# REV_LIMTER_ARDUINO_NANO.net
KiCad netlist of a schematic drawn in EAGLE
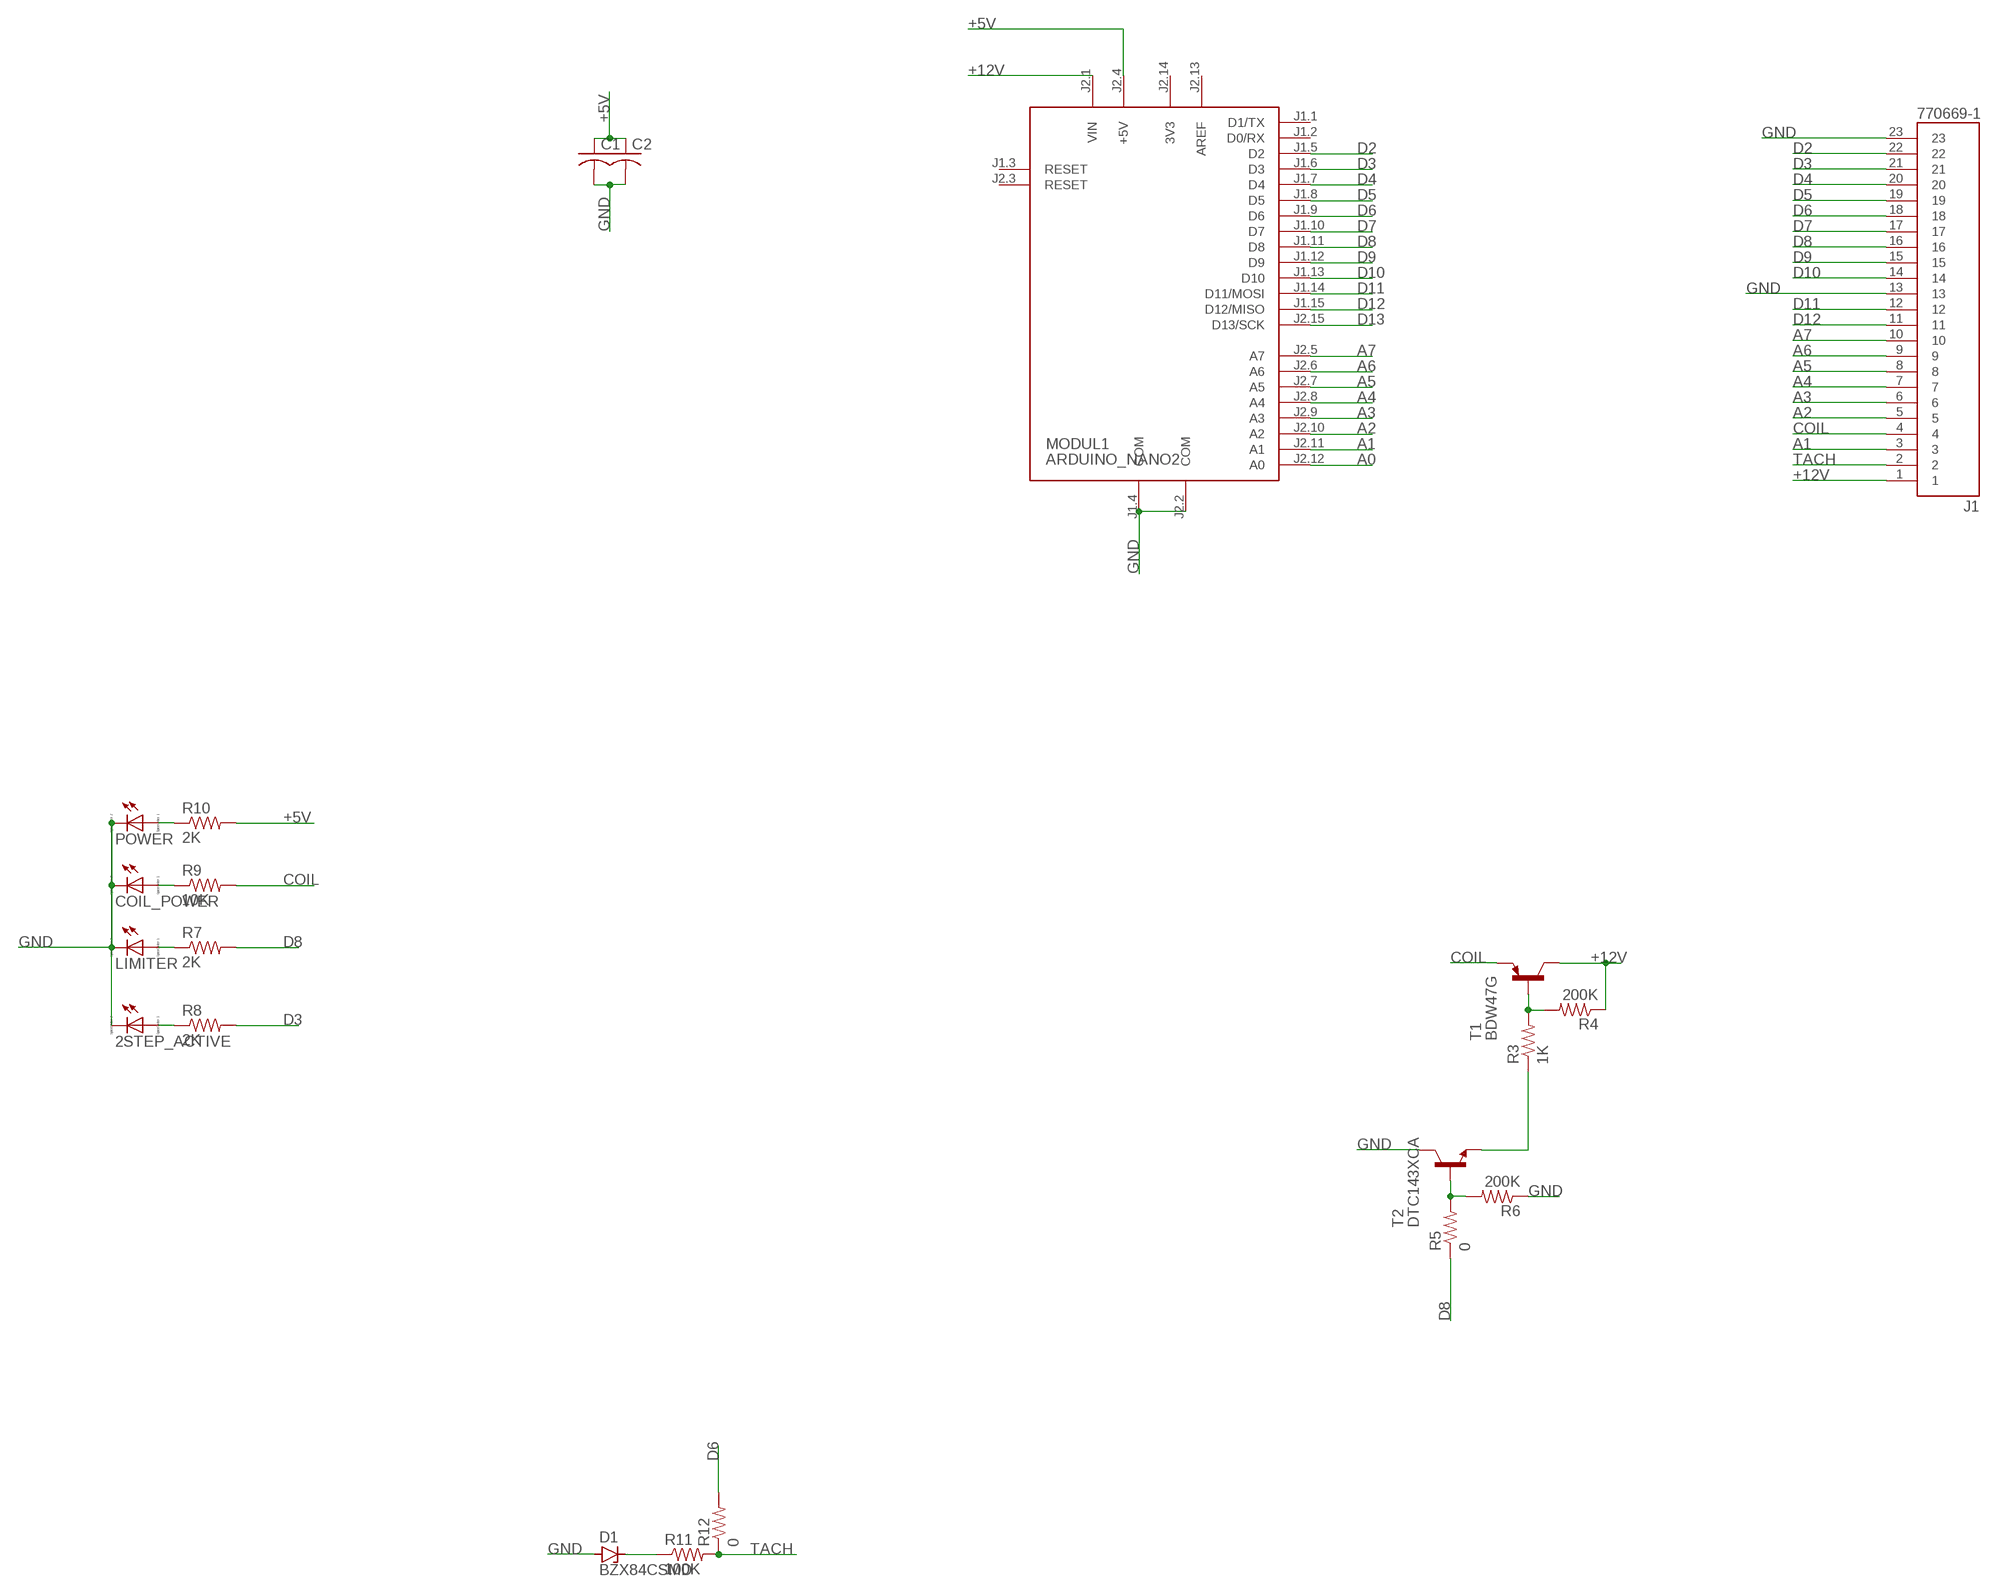
[diagram p0: schematic, sheet 1]

(export (version "E")
  (design (tool "Eeschema 10.0.6"))
  (components
    (comp (ref "2STEP_ACTIVE")
      (value "LED_E")
      (footprint "eagle-import:LED_1206")
      (libsource (lib "eagle-import") (part "LED_E"))
    )
    (comp (ref "C1")
      (value "C-USC1206")
      (footprint "eagle-import:C1206")
      (libsource (lib "eagle-import") (part "C-USC1206"))
    )
    (comp (ref "C2")
      (value "C-USC1206")
      (footprint "eagle-import:C1206")
      (libsource (lib "eagle-import") (part "C-USC1206"))
    )
    (comp (ref "COIL_POWER")
      (value "LED_E")
      (footprint "eagle-import:LED_1206")
      (libsource (lib "eagle-import") (part "LED_E"))
    )
    (comp (ref "D1")
      (value "BZX84CSMD")
      (footprint "eagle-import:TO236")
      (libsource (lib "eagle-import") (part "BZX84CSMD"))
    )
    (comp (ref "J1")
      (value "770669-1")
      (footprint "eagle-import:TE_770669-1")
      (fields (field (name "MF") "TE Connectivity"))
      (libsource (lib "eagle-import") (part "770669-1"))
    )
    (comp (ref "LIMITER")
      (value "LED_E")
      (footprint "eagle-import:LED_1206")
      (libsource (lib "eagle-import") (part "LED_E"))
    )
    (comp (ref "MODUL1")
      (value "ARDUINO_NANO2")
      (footprint "eagle-import:ARDUINO_NANO2")
      (libsource (lib "eagle-import") (part "ARDUINO_NANO2"))
    )
    (comp (ref "POWER")
      (value "LED_E")
      (footprint "eagle-import:LED_1206")
      (libsource (lib "eagle-import") (part "LED_E"))
    )
    (comp (ref "R3")
      (value "1K")
      (footprint "eagle-import:M0805")
      (libsource (lib "eagle-import") (part "R-US_M0805"))
    )
    (comp (ref "R4")
      (value "200K")
      (footprint "eagle-import:M0805")
      (libsource (lib "eagle-import") (part "R-US_M0805"))
    )
    (comp (ref "R5")
      (value "0")
      (footprint "eagle-import:M0805")
      (libsource (lib "eagle-import") (part "R-US_M0805"))
    )
    (comp (ref "R6")
      (value "200K")
      (footprint "eagle-import:M0805")
      (libsource (lib "eagle-import") (part "R-US_M0805"))
    )
    (comp (ref "R7")
      (value "2K")
      (footprint "eagle-import:R1206")
      (libsource (lib "eagle-import") (part "R-US_R1206"))
    )
    (comp (ref "R8")
      (value "2K")
      (footprint "eagle-import:R1206")
      (libsource (lib "eagle-import") (part "R-US_R1206"))
    )
    (comp (ref "R9")
      (value "10K")
      (footprint "eagle-import:R1206")
      (libsource (lib "eagle-import") (part "R-US_R1206"))
    )
    (comp (ref "R10")
      (value "2K")
      (footprint "eagle-import:R1206")
      (libsource (lib "eagle-import") (part "R-US_R1206"))
    )
    (comp (ref "R11")
      (value "100K")
      (footprint "eagle-import:R1206")
      (libsource (lib "eagle-import") (part "R-US_R1206"))
    )
    (comp (ref "R12")
      (value "0")
      (footprint "eagle-import:R0805")
      (libsource (lib "eagle-import") (part "R-US_R0805"))
    )
    (comp (ref "T1")
      (value "BDW47G")
      (footprint "eagle-import:TO220V")
      (libsource (lib "eagle-import") (part "-PNP-TO220V"))
    )
    (comp (ref "T2")
      (value "DTC143XCA")
      (footprint "eagle-import:SOT23-BEC")
      (libsource (lib "eagle-import") (part "-NPN-SOT23-BECBC808"))
    )
  )
  (nets
    (net (code "1") (name "/+5V") (class "Default")
      (node (ref "C1") (pin "1") (pinfunction "1_1") (pintype "passive"))
      (node (ref "C2") (pin "1") (pinfunction "1_1") (pintype "passive"))
      (node (ref "MODUL1") (pin "J2.4") (pinfunction "+5V_J2.4") (pintype "power_in"))
      (node (ref "R10") (pin "2") (pinfunction "2_2") (pintype "passive"))
    )
    (net (code "2") (name "/+12V") (class "Default")
      (node (ref "J1") (pin "1") (pinfunction "1_1") (pintype "passive"))
      (node (ref "MODUL1") (pin "J2.1") (pinfunction "VIN_J2.1") (pintype "power_in"))
      (node (ref "R4") (pin "1") (pinfunction "1_1") (pintype "passive"))
      (node (ref "T1") (pin "2") (pinfunction "C_2") (pintype "passive"))
    )
    (net (code "3") (name "/3V3") (class "Default")
      (node (ref "MODUL1") (pin "J2.14") (pinfunction "3V3_J2.14") (pintype "power_in"))
    )
    (net (code "4") (name "/A0") (class "Default")
      (node (ref "MODUL1") (pin "J2.12") (pinfunction "A0_J2.12") (pintype "bidirectional"))
    )
    (net (code "5") (name "/A1") (class "Default")
      (node (ref "J1") (pin "3") (pinfunction "3_3") (pintype "passive"))
      (node (ref "MODUL1") (pin "J2.11") (pinfunction "A1_J2.11") (pintype "bidirectional"))
    )
    (net (code "6") (name "/A2") (class "Default")
      (node (ref "J1") (pin "5") (pinfunction "5_5") (pintype "passive"))
      (node (ref "MODUL1") (pin "J2.10") (pinfunction "A2_J2.10") (pintype "bidirectional"))
    )
    (net (code "7") (name "/A3") (class "Default")
      (node (ref "J1") (pin "6") (pinfunction "6_6") (pintype "passive"))
      (node (ref "MODUL1") (pin "J2.9") (pinfunction "A3_J2.9") (pintype "bidirectional"))
    )
    (net (code "8") (name "/A4") (class "Default")
      (node (ref "J1") (pin "7") (pinfunction "7_7") (pintype "passive"))
      (node (ref "MODUL1") (pin "J2.8") (pinfunction "A4_J2.8") (pintype "bidirectional"))
    )
    (net (code "9") (name "/A5") (class "Default")
      (node (ref "J1") (pin "8") (pinfunction "8_8") (pintype "passive"))
      (node (ref "MODUL1") (pin "J2.7") (pinfunction "A5_J2.7") (pintype "bidirectional"))
    )
    (net (code "10") (name "/A6") (class "Default")
      (node (ref "J1") (pin "9") (pinfunction "9_9") (pintype "passive"))
      (node (ref "MODUL1") (pin "J2.6") (pinfunction "A6_J2.6") (pintype "bidirectional"))
    )
    (net (code "11") (name "/A7") (class "Default")
      (node (ref "J1") (pin "10") (pinfunction "10_10") (pintype "passive"))
      (node (ref "MODUL1") (pin "J2.5") (pinfunction "A7_J2.5") (pintype "bidirectional"))
    )
    (net (code "12") (name "/AREF") (class "Default")
      (node (ref "MODUL1") (pin "J2.13") (pinfunction "AREF_J2.13") (pintype "power_in"))
    )
    (net (code "13") (name "/COIL") (class "Default")
      (node (ref "J1") (pin "4") (pinfunction "4_4") (pintype "passive"))
      (node (ref "R9") (pin "2") (pinfunction "2_2") (pintype "passive"))
      (node (ref "T1") (pin "3") (pinfunction "E_3") (pintype "passive"))
    )
    (net (code "14") (name "/D2") (class "Default")
      (node (ref "J1") (pin "22") (pinfunction "22_22") (pintype "passive"))
      (node (ref "MODUL1") (pin "J1.5") (pinfunction "D2_J1.5") (pintype "bidirectional"))
    )
    (net (code "15") (name "/D3") (class "Default")
      (node (ref "J1") (pin "21") (pinfunction "21_21") (pintype "passive"))
      (node (ref "MODUL1") (pin "J1.6") (pinfunction "D3_J1.6") (pintype "bidirectional"))
      (node (ref "R8") (pin "2") (pinfunction "2_2") (pintype "passive"))
    )
    (net (code "16") (name "/D4") (class "Default")
      (node (ref "J1") (pin "20") (pinfunction "20_20") (pintype "passive"))
      (node (ref "MODUL1") (pin "J1.7") (pinfunction "D4_J1.7") (pintype "bidirectional"))
    )
    (net (code "17") (name "/D5") (class "Default")
      (node (ref "J1") (pin "19") (pinfunction "19_19") (pintype "passive"))
      (node (ref "MODUL1") (pin "J1.8") (pinfunction "D5_J1.8") (pintype "bidirectional"))
    )
    (net (code "18") (name "/D6") (class "Default")
      (node (ref "J1") (pin "18") (pinfunction "18_18") (pintype "passive"))
      (node (ref "MODUL1") (pin "J1.9") (pinfunction "D6_J1.9") (pintype "bidirectional"))
      (node (ref "R12") (pin "2") (pinfunction "2_2") (pintype "passive"))
    )
    (net (code "19") (name "/D7") (class "Default")
      (node (ref "J1") (pin "17") (pinfunction "17_17") (pintype "passive"))
      (node (ref "MODUL1") (pin "J1.10") (pinfunction "D7_J1.10") (pintype "bidirectional"))
    )
    (net (code "20") (name "/D8") (class "Default")
      (node (ref "J1") (pin "16") (pinfunction "16_16") (pintype "passive"))
      (node (ref "MODUL1") (pin "J1.11") (pinfunction "D8_J1.11") (pintype "bidirectional"))
      (node (ref "R5") (pin "1") (pinfunction "1_1") (pintype "passive"))
      (node (ref "R7") (pin "2") (pinfunction "2_2") (pintype "passive"))
    )
    (net (code "21") (name "/D9") (class "Default")
      (node (ref "J1") (pin "15") (pinfunction "15_15") (pintype "passive"))
      (node (ref "MODUL1") (pin "J1.12") (pinfunction "D9_J1.12") (pintype "bidirectional"))
    )
    (net (code "22") (name "/D10") (class "Default")
      (node (ref "J1") (pin "14") (pinfunction "14_14") (pintype "passive"))
      (node (ref "MODUL1") (pin "J1.13") (pinfunction "D10_J1.13") (pintype "bidirectional"))
    )
    (net (code "23") (name "/D11") (class "Default")
      (node (ref "J1") (pin "12") (pinfunction "12_12") (pintype "passive"))
      (node (ref "MODUL1") (pin "J1.14") (pinfunction "D11/MOSI_J1.14") (pintype "bidirectional"))
    )
    (net (code "24") (name "/D12") (class "Default")
      (node (ref "J1") (pin "11") (pinfunction "11_11") (pintype "passive"))
      (node (ref "MODUL1") (pin "J1.15") (pinfunction "D12/MISO_J1.15") (pintype "bidirectional"))
    )
    (net (code "25") (name "/D13") (class "Default")
      (node (ref "MODUL1") (pin "J2.15") (pinfunction "D13/SCK_J2.15") (pintype "bidirectional"))
    )
    (net (code "26") (name "/GND") (class "Default")
      (node (ref "2STEP_ACTIVE") (pin "C") (pinfunction "C_C") (pintype "passive"))
      (node (ref "C1") (pin "2") (pinfunction "2_2") (pintype "passive"))
      (node (ref "C2") (pin "2") (pinfunction "2_2") (pintype "passive"))
      (node (ref "COIL_POWER") (pin "C") (pinfunction "C_C") (pintype "passive"))
      (node (ref "D1") (pin "A") (pinfunction "A_A") (pintype "passive"))
      (node (ref "J1") (pin "13") (pinfunction "13_13") (pintype "passive"))
      (node (ref "J1") (pin "23") (pinfunction "23_23") (pintype "passive"))
      (node (ref "LIMITER") (pin "C") (pinfunction "C_C") (pintype "passive"))
      (node (ref "MODUL1") (pin "J1.4") (pinfunction "COM_J1.4") (pintype "power_in"))
      (node (ref "MODUL1") (pin "J2.2") (pinfunction "COM_J2.2") (pintype "power_in"))
      (node (ref "POWER") (pin "C") (pinfunction "C_C") (pintype "passive"))
      (node (ref "R6") (pin "1") (pinfunction "1_1") (pintype "passive"))
      (node (ref "T2") (pin "C") (pinfunction "C_C") (pintype "passive"))
    )
    (net (code "27") (name "/TACH") (class "Default")
      (node (ref "J1") (pin "2") (pinfunction "2_2") (pintype "passive"))
      (node (ref "R11") (pin "2") (pinfunction "2_2") (pintype "passive"))
      (node (ref "R12") (pin "1") (pinfunction "1_1") (pintype "passive"))
    )
    (net (code "28") (name "Net-(2STEP_ACTIVE-PadA)") (class "Default")
      (node (ref "2STEP_ACTIVE") (pin "A") (pinfunction "A_A") (pintype "passive"))
      (node (ref "R8") (pin "1") (pinfunction "1_1") (pintype "passive"))
    )
    (net (code "29") (name "Net-(COIL_POWER-PadA)") (class "Default")
      (node (ref "COIL_POWER") (pin "A") (pinfunction "A_A") (pintype "passive"))
      (node (ref "R9") (pin "1") (pinfunction "1_1") (pintype "passive"))
    )
    (net (code "30") (name "Net-(D1-PadC)") (class "Default")
      (node (ref "D1") (pin "C") (pinfunction "C_C") (pintype "passive"))
      (node (ref "R11") (pin "1") (pinfunction "1_1") (pintype "passive"))
    )
    (net (code "31") (name "Net-(LIMITER-PadA)") (class "Default")
      (node (ref "LIMITER") (pin "A") (pinfunction "A_A") (pintype "passive"))
      (node (ref "R7") (pin "1") (pinfunction "1_1") (pintype "passive"))
    )
    (net (code "32") (name "Net-(POWER-PadA)") (class "Default")
      (node (ref "POWER") (pin "A") (pinfunction "A_A") (pintype "passive"))
      (node (ref "R10") (pin "1") (pinfunction "1_1") (pintype "passive"))
    )
    (net (code "33") (name "Net-(R3-Pad1)") (class "Default")
      (node (ref "R3") (pin "1") (pinfunction "1_1") (pintype "passive"))
      (node (ref "T2") (pin "E") (pinfunction "E_E") (pintype "passive"))
    )
    (net (code "34") (name "Net-(R5-Pad2)") (class "Default")
      (node (ref "R5") (pin "2") (pinfunction "2_2") (pintype "passive"))
      (node (ref "R6") (pin "2") (pinfunction "2_2") (pintype "passive"))
      (node (ref "T2") (pin "B") (pinfunction "B_B") (pintype "passive"))
    )
    (net (code "35") (name "Net-(T1-B)") (class "Default")
      (node (ref "R3") (pin "2") (pinfunction "2_2") (pintype "passive"))
      (node (ref "R4") (pin "2") (pinfunction "2_2") (pintype "passive"))
      (node (ref "T1") (pin "1") (pinfunction "B_1") (pintype "passive"))
    )
    (net (code "36") (name "unconnected-(MODUL1-D0{slash}RX-PadJ1.2)") (class "Default")
      (node (ref "MODUL1") (pin "J1.2") (pinfunction "D0/RX_J1.2") (pintype "bidirectional"))
    )
    (net (code "37") (name "unconnected-(MODUL1-D1{slash}TX-PadJ1.1)") (class "Default")
      (node (ref "MODUL1") (pin "J1.1") (pinfunction "D1/TX_J1.1") (pintype "bidirectional"))
    )
    (net (code "38") (name "unconnected-(MODUL1-RESET-PadJ1.3)") (class "Default")
      (node (ref "MODUL1") (pin "J1.3") (pinfunction "RESET_J1.3") (pintype "bidirectional"))
    )
    (net (code "39") (name "unconnected-(MODUL1-RESET-PadJ2.3)") (class "Default")
      (node (ref "MODUL1") (pin "J2.3") (pinfunction "RESET_J2.3") (pintype "bidirectional"))
    )
  )
)
